# SCH_18f4550_2023-06-13.net
KiCad netlist of a schematic drawn in EasyEDA
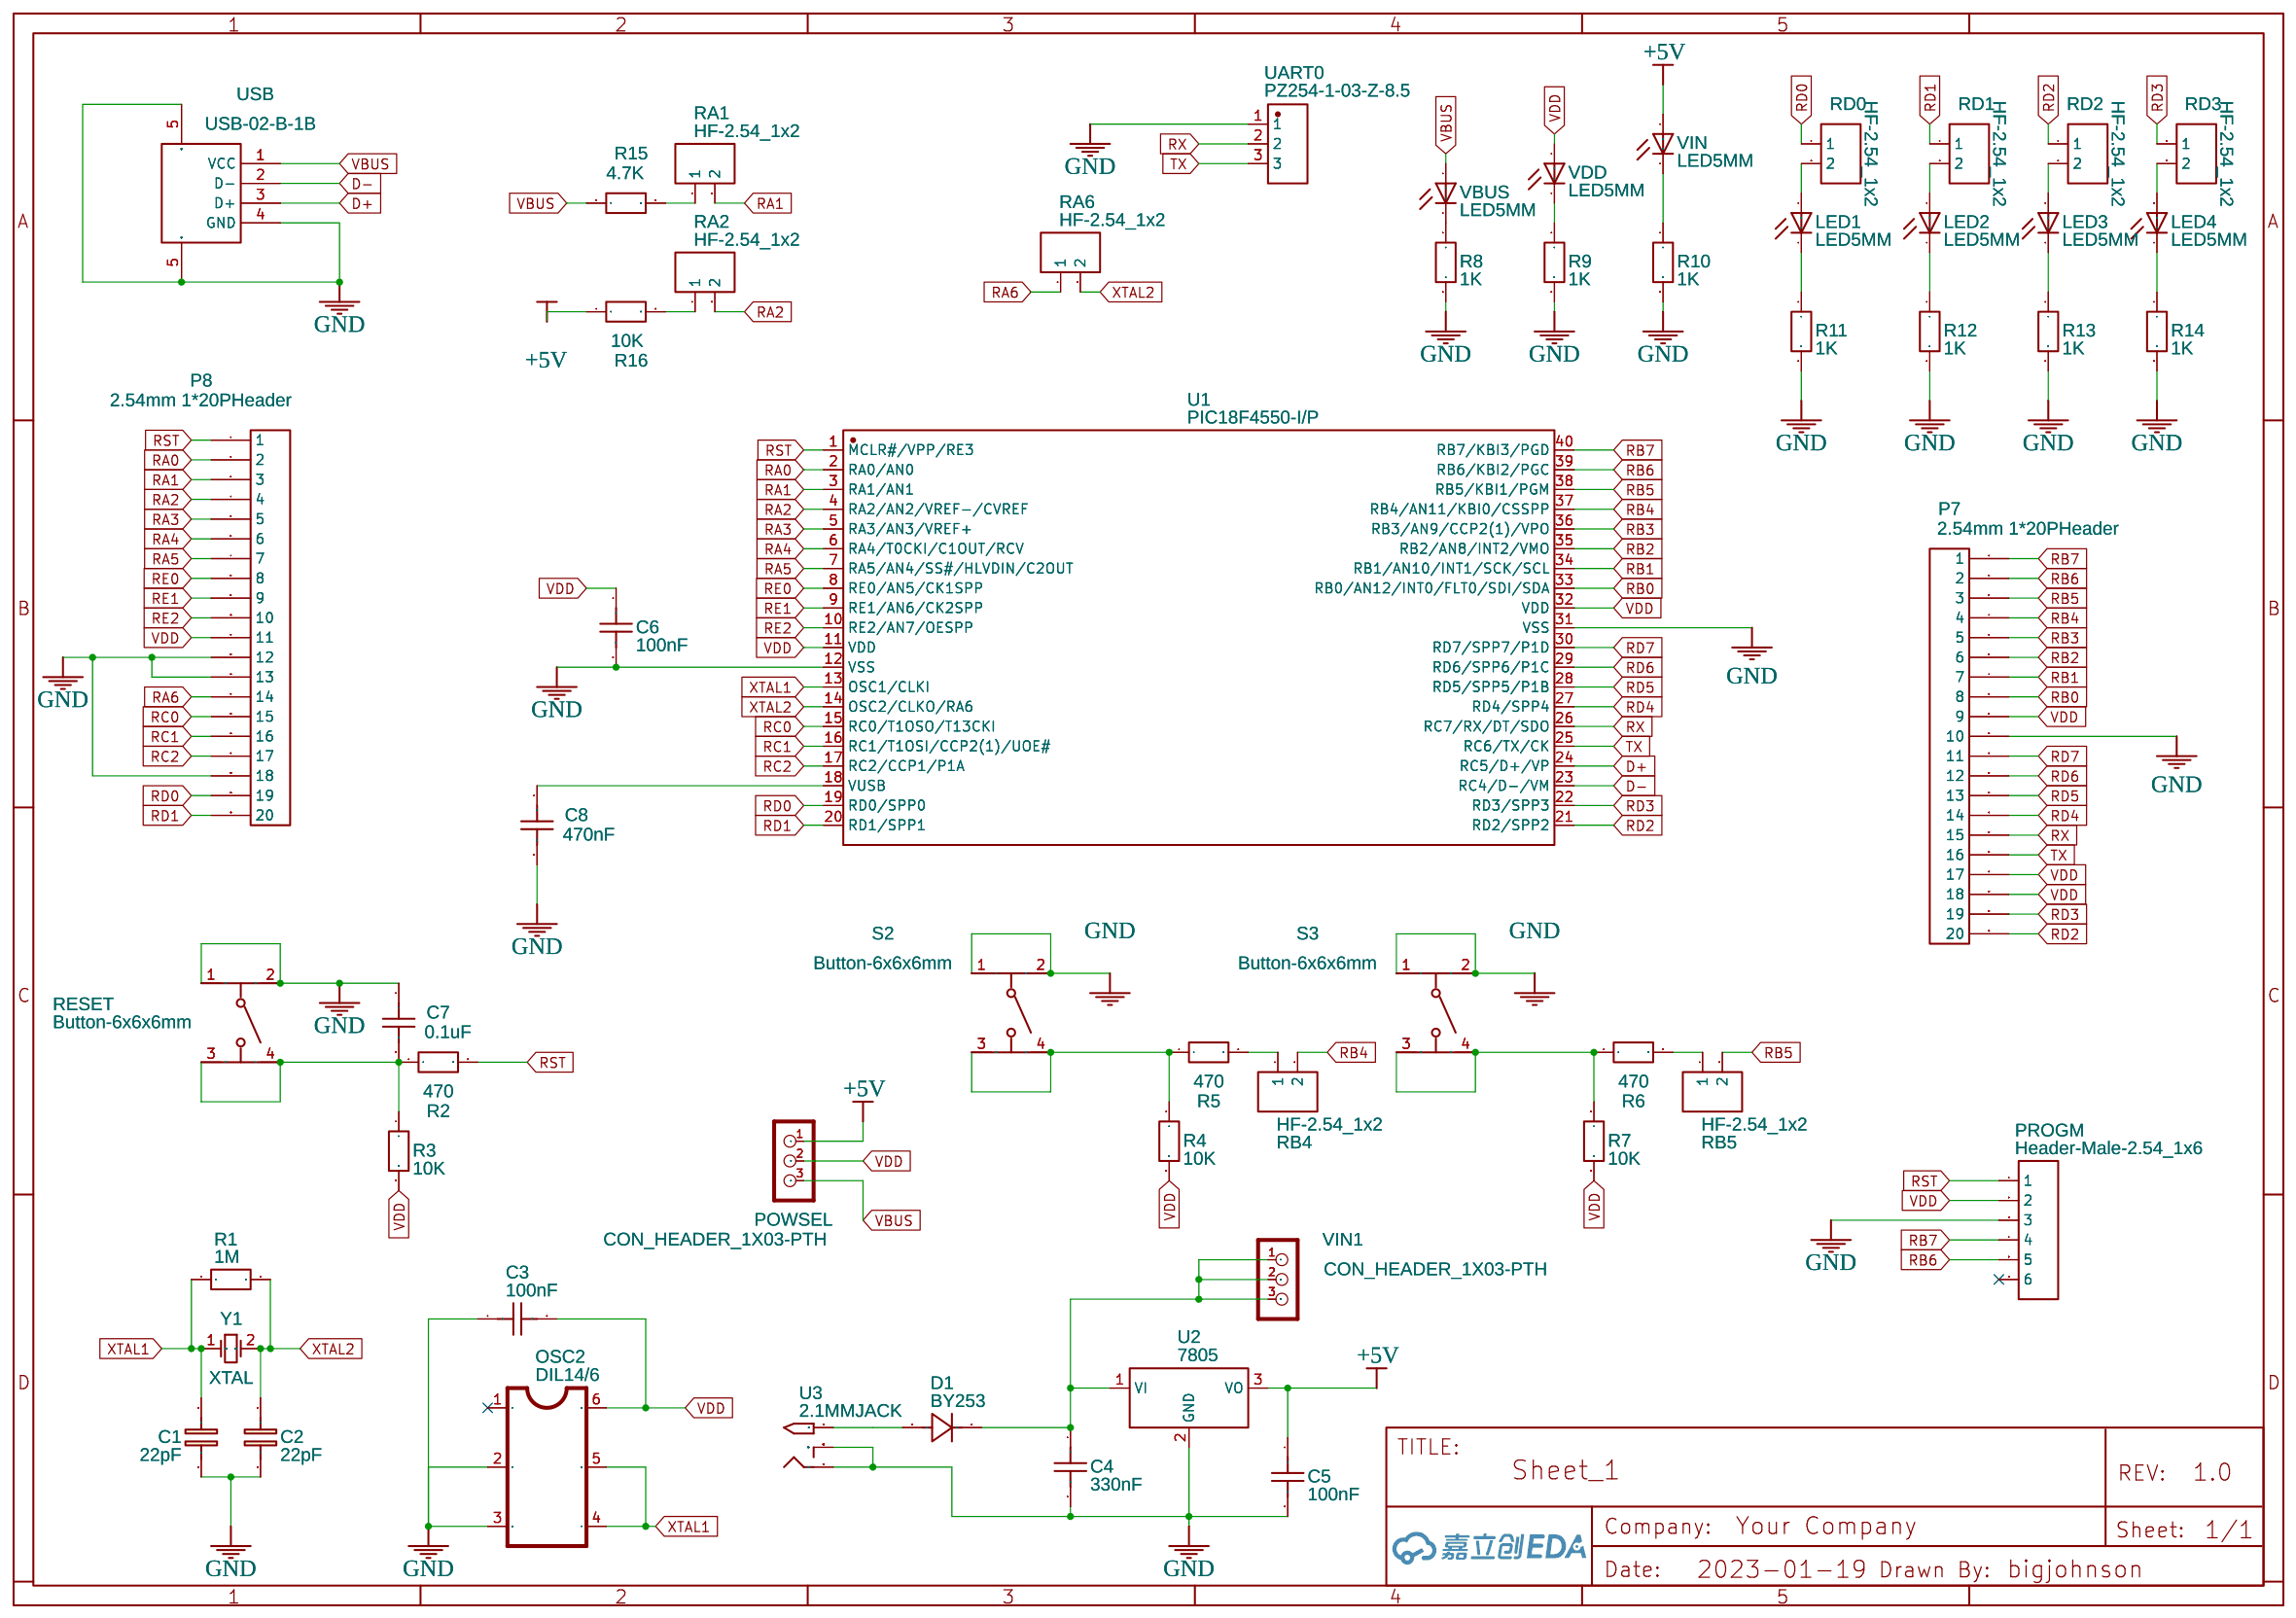
[diagram p0: schematic sheet]

(export (version "E")
  (design (tool "Eeschema 10.0.6"))
  (components
    (comp (ref "C1")
      (value "22pF")
      (fields (field (name "BOM_Supplier Part") "9000274010"))
      (libsource (lib "") (part "20pF copy"))
    )
    (comp (ref "C2")
      (value "22pF")
      (fields (field (name "BOM_Supplier Part") "9000274010"))
      (libsource (lib "") (part "20pF copy"))
    )
    (comp (ref "C3")
      (value "100nF")
      (fields
        (field (name "BOM_Manufacturer Part") "CT4-0805B103 K500")
        (field (name "BOM_Supplier Part") "C8033")
      )
      (libsource (lib "") (part "CT4-0805B103 K500_1"))
    )
    (comp (ref "C4")
      (value "330nF")
      (fields
        (field (name "BOM_Manufacturer Part") "CT4-0805B103 K500")
        (field (name "BOM_Supplier Part") "C8033")
      )
      (libsource (lib "") (part "CT4-0805B103 K500"))
    )
    (comp (ref "C5")
      (value "100nF")
      (fields
        (field (name "BOM_Manufacturer Part") "CT4-0805B103 K500")
        (field (name "BOM_Supplier Part") "C8033")
      )
      (libsource (lib "") (part "CT4-0805B103 K500"))
    )
    (comp (ref "C6")
      (value "100nF")
      (fields
        (field (name "BOM_Manufacturer Part") "CT4-0805B103 K500")
        (field (name "BOM_Supplier Part") "C8033")
      )
      (libsource (lib "") (part "CT4-0805B103 K500"))
    )
    (comp (ref "C7")
      (value "0.1uF")
      (fields
        (field (name "BOM_Manufacturer Part") "CT4-0805B103 K500")
        (field (name "BOM_Supplier Part") "C8033")
      )
      (libsource (lib "") (part "CT4-0805B103 K500"))
    )
    (comp (ref "C8")
      (value "470nF")
      (fields
        (field (name "BOM_Manufacturer Part") "CT4-0805B103 K500")
        (field (name "BOM_Supplier Part") "C8033")
      )
      (libsource (lib "") (part "CT4-0805B103 K500"))
    )
    (comp (ref "D1")
      (value "BY253")
      (fields (field (name "BOM_Manufacturer Part") "MUR460") (field (name "BOM_Supplier Part") "C2990844"))
      (libsource (lib "") (part "MUR460_C2990844"))
    )
    (comp (ref "LED1") (value "LED5MM") (libsource (lib "") (part "LED5MM")))
    (comp (ref "LED2") (value "LED5MM") (libsource (lib "") (part "LED5MM")))
    (comp (ref "LED3") (value "LED5MM") (libsource (lib "") (part "LED5MM")))
    (comp (ref "LED4") (value "LED5MM") (libsource (lib "") (part "LED5MM")))
    (comp (ref "OSC2") (value "DIL14/6") (libsource (lib "") (part "DIL14/3")))
    (comp (ref "P7")
      (value "2.54mm 1*20PHeader")
      (fields (field (name "BOM_Supplier Part") "C50981"))
      (libsource (lib "") (part "2.54mm 1*20PHeader"))
    )
    (comp (ref "P8")
      (value "2.54mm 1*20PHeader")
      (fields (field (name "BOM_Supplier Part") "C50981"))
      (libsource (lib "") (part "2.54mm 1*20PHeader_1"))
    )
    (comp (ref "POWSEL") (value "CON_HEADER_1X03-PTH") (libsource (lib "") (part "CON_HEADER_1X03-PTH")))
    (comp (ref "PROGM")
      (value "Header-Male-2.54_1x6")
      (fields
        (field (name "BOM_Manufacturer Part") "2.54-1x6P直针")
        (field (name "BOM_Supplier Part") "C37208")
      )
      (libsource (lib "") (part "Header-Male-2.54_1x6"))
    )
    (comp (ref "R1") (value "1M") (libsource (lib "") (part "Res_AXIAL-0.4(1/4W)_EU_1")))
    (comp (ref "R2") (value "470") (libsource (lib "") (part "Res_AXIAL-0.4(1/4W)_EU_1")))
    (comp (ref "R3") (value "10K") (libsource (lib "") (part "Res_AXIAL-0.4(1/4W)_EU")))
    (comp (ref "R4") (value "10K") (libsource (lib "") (part "Res_AXIAL-0.4(1/4W)_EU")))
    (comp (ref "R5") (value "470") (libsource (lib "") (part "Res_AXIAL-0.4(1/4W)_EU_1")))
    (comp (ref "R6") (value "470") (libsource (lib "") (part "Res_AXIAL-0.4(1/4W)_EU_1")))
    (comp (ref "R7") (value "10K") (libsource (lib "") (part "Res_AXIAL-0.4(1/4W)_EU")))
    (comp (ref "R8") (value "1K") (libsource (lib "") (part "Res_AXIAL-0.4(1/4W)_EU")))
    (comp (ref "R9") (value "1K") (libsource (lib "") (part "Res_AXIAL-0.4(1/4W)_EU")))
    (comp (ref "R10") (value "1K") (libsource (lib "") (part "Res_AXIAL-0.4(1/4W)_EU")))
    (comp (ref "R11") (value "1K") (libsource (lib "") (part "Res_AXIAL-0.4(1/4W)_EU")))
    (comp (ref "R12") (value "1K") (libsource (lib "") (part "Res_AXIAL-0.4(1/4W)_EU")))
    (comp (ref "R13") (value "1K") (libsource (lib "") (part "Res_AXIAL-0.4(1/4W)_EU")))
    (comp (ref "R14") (value "1K") (libsource (lib "") (part "Res_AXIAL-0.4(1/4W)_EU")))
    (comp (ref "R15") (value "4.7K") (libsource (lib "") (part "Res_AXIAL-0.4(1/4W)_EU_1")))
    (comp (ref "R16") (value "10K") (libsource (lib "") (part "Res_AXIAL-0.4(1/4W)_EU_1")))
    (comp (ref "RA1")
      (value "HF-2.54_1x2")
      (fields (field (name "BOM_Manufacturer Part") "2.54-1*2P母") (field (name "BOM_Supplier Part") "C49661"))
      (libsource (lib "") (part "Header-Female-2.54_1x2"))
    )
    (comp (ref "RA2")
      (value "HF-2.54_1x2")
      (fields (field (name "BOM_Manufacturer Part") "2.54-1*2P母") (field (name "BOM_Supplier Part") "C49661"))
      (libsource (lib "") (part "Header-Female-2.54_1x2"))
    )
    (comp (ref "RA6")
      (value "HF-2.54_1x2")
      (fields (field (name "BOM_Manufacturer Part") "2.54-1*2P母") (field (name "BOM_Supplier Part") "C49661"))
      (libsource (lib "") (part "Header-Female-2.54_1x2"))
    )
    (comp (ref "RB4")
      (value "HF-2.54_1x2")
      (fields (field (name "BOM_Manufacturer Part") "2.54-1*2P母") (field (name "BOM_Supplier Part") "C49661"))
      (libsource (lib "") (part "Header-Female-2.54_1x2_2"))
    )
    (comp (ref "RB5")
      (value "HF-2.54_1x2")
      (fields (field (name "BOM_Manufacturer Part") "2.54-1*2P母") (field (name "BOM_Supplier Part") "C49661"))
      (libsource (lib "") (part "Header-Female-2.54_1x2_2"))
    )
    (comp (ref "RD0")
      (value "HF-2.54_1x2")
      (fields (field (name "BOM_Manufacturer Part") "2.54-1*2P母") (field (name "BOM_Supplier Part") "C49661"))
      (libsource (lib "") (part "Header-Female-2.54_1x2_1"))
    )
    (comp (ref "RD1")
      (value "HF-2.54_1x2")
      (fields (field (name "BOM_Manufacturer Part") "2.54-1*2P母") (field (name "BOM_Supplier Part") "C49661"))
      (libsource (lib "") (part "Header-Female-2.54_1x2_1"))
    )
    (comp (ref "RD2")
      (value "HF-2.54_1x2")
      (fields (field (name "BOM_Manufacturer Part") "2.54-1*2P母") (field (name "BOM_Supplier Part") "C49661"))
      (libsource (lib "") (part "Header-Female-2.54_1x2_1"))
    )
    (comp (ref "RD3")
      (value "HF-2.54_1x2")
      (fields (field (name "BOM_Manufacturer Part") "2.54-1*2P母") (field (name "BOM_Supplier Part") "C49661"))
      (libsource (lib "") (part "Header-Female-2.54_1x2_1"))
    )
    (comp (ref "RESET")
      (value "Button-6x6x6mm")
      (fields
        (field (name "BOM_Manufacturer Part") "Switch,6*6*6Plastic head,260G, 0.25mm,Straight line")
        (field (name "BOM_Supplier Part") "C71836")
      )
      (libsource (lib "") (part "Button-6x6x6mm_1"))
    )
    (comp (ref "S2")
      (value "Button-6x6x6mm")
      (fields
        (field (name "BOM_Manufacturer Part") "Switch,6*6*6Plastic head,260G, 0.25mm,Straight line")
        (field (name "BOM_Supplier Part") "C71836")
      )
      (libsource (lib "") (part "Button-6x6x6mm"))
    )
    (comp (ref "S3")
      (value "Button-6x6x6mm")
      (fields
        (field (name "BOM_Manufacturer Part") "Switch,6*6*6Plastic head,260G, 0.25mm,Straight line")
        (field (name "BOM_Supplier Part") "C71836")
      )
      (libsource (lib "") (part "Button-6x6x6mm"))
    )
    (comp (ref "U1")
      (value "PIC18F4550-I/P")
      (fields (field (name "BOM_Supplier Part") "C648001"))
      (libsource (lib "") (part "PIC18F4550-I/P"))
    )
    (comp (ref "U2")
      (value "7805")
      (fields (field (name "BOM_Supplier Part") "C305416"))
      (libsource (lib "") (part "7805"))
    )
    (comp (ref "U3") (value "2.1MMJACK") (libsource (lib "") (part "2.1MMJACK")))
    (comp (ref "UART0")
      (value "PZ254-1-03-Z-8.5")
      (fields (field (name "BOM_Supplier Part") "C2894926"))
      (libsource (lib "") (part "PZ254-1-03-Z-8.5"))
    )
    (comp (ref "USB")
      (value "USB-02-B-1B")
      (fields (field (name "BOM_Supplier Part") "C718028"))
      (libsource (lib "") (part "USB-02-B-1B"))
    )
    (comp (ref "VBUS") (value "LED5MM") (libsource (lib "") (part "LED5MM_3")))
    (comp (ref "VDD") (value "LED5MM") (libsource (lib "") (part "LED5MM_1")))
    (comp (ref "VIN") (value "LED5MM") (libsource (lib "") (part "LED5MM_2")))
    (comp (ref "VIN1") (value "CON_HEADER_1X03-PTH") (libsource (lib "") (part "CON_HEADER_1X03-PTH_1")))
    (comp (ref "Y1") (value "XTAL") (libsource (lib "") (part "XTAL")))
  )
  (nets
    (net (code "1") (name "+5V") (class "Default")
      (node (ref "C5") (pin "1") (pinfunction "1_1") (pintype "unspecified"))
      (node (ref "POWSEL") (pin "1") (pinfunction "1_1") (pintype "unspecified"))
      (node (ref "R16") (pin "1") (pinfunction "1_1") (pintype "unspecified"))
      (node (ref "U2") (pin "3") (pinfunction "VO_3") (pintype "unspecified"))
      (node (ref "VIN") (pin "A") (pinfunction "A_A") (pintype "unspecified"))
    )
    (net (code "2") (name "D+") (class "Default")
      (node (ref "U1") (pin "24") (pinfunction "RC5/D+/VP_24") (pintype "unspecified"))
      (node (ref "USB") (pin "3") (pinfunction "D+_3") (pintype "input"))
    )
    (net (code "3") (name "D-") (class "Default")
      (node (ref "U1") (pin "23") (pinfunction "RC4/D-/VM_23") (pintype "unspecified"))
      (node (ref "USB") (pin "2") (pinfunction "D-_2") (pintype "input"))
    )
    (net (code "4") (name "GND") (class "Default")
      (node (ref "C1") (pin "2") (pinfunction "1_2") (pintype "unspecified"))
      (node (ref "C2") (pin "2") (pinfunction "1_2") (pintype "unspecified"))
      (node (ref "C3") (pin "1") (pinfunction "1_1") (pintype "unspecified"))
      (node (ref "C4") (pin "2") (pinfunction "2_2") (pintype "unspecified"))
      (node (ref "C5") (pin "2") (pinfunction "2_2") (pintype "unspecified"))
      (node (ref "C6") (pin "2") (pinfunction "2_2") (pintype "unspecified"))
      (node (ref "C7") (pin "1") (pinfunction "1_1") (pintype "unspecified"))
      (node (ref "C8") (pin "2") (pinfunction "2_2") (pintype "unspecified"))
      (node (ref "OSC2") (pin "2") (pinfunction "2_2") (pintype "unspecified"))
      (node (ref "OSC2") (pin "3") (pinfunction "3_3") (pintype "unspecified"))
      (node (ref "P7") (pin "10") (pinfunction "10_10") (pintype "input"))
      (node (ref "P8") (pin "12") (pinfunction "12_12") (pintype "input"))
      (node (ref "P8") (pin "13") (pinfunction "13_13") (pintype "input"))
      (node (ref "P8") (pin "18") (pinfunction "18_18") (pintype "input"))
      (node (ref "PROGM") (pin "3") (pinfunction "3_3") (pintype "input"))
      (node (ref "R10") (pin "2") (pinfunction "2_2") (pintype "unspecified"))
      (node (ref "R11") (pin "2") (pinfunction "2_2") (pintype "unspecified"))
      (node (ref "R12") (pin "2") (pinfunction "2_2") (pintype "unspecified"))
      (node (ref "R13") (pin "2") (pinfunction "2_2") (pintype "unspecified"))
      (node (ref "R14") (pin "2") (pinfunction "2_2") (pintype "unspecified"))
      (node (ref "R8") (pin "2") (pinfunction "2_2") (pintype "unspecified"))
      (node (ref "R9") (pin "2") (pinfunction "2_2") (pintype "unspecified"))
      (node (ref "RESET") (pin "1") (pinfunction "1_1") (pintype "unspecified"))
      (node (ref "RESET") (pin "2") (pinfunction "2_2") (pintype "unspecified"))
      (node (ref "S2") (pin "1") (pinfunction "1_1") (pintype "unspecified"))
      (node (ref "S2") (pin "2") (pinfunction "2_2") (pintype "unspecified"))
      (node (ref "S3") (pin "1") (pinfunction "1_1") (pintype "unspecified"))
      (node (ref "S3") (pin "2") (pinfunction "2_2") (pintype "unspecified"))
      (node (ref "U1") (pin "12") (pinfunction "VSS_12") (pintype "unspecified"))
      (node (ref "U1") (pin "31") (pinfunction "VSS_31") (pintype "unspecified"))
      (node (ref "U2") (pin "2") (pinfunction "GND_2") (pintype "unspecified"))
      (node (ref "U3") (pin "RING") (pinfunction "RING_RING") (pintype "unspecified"))
      (node (ref "U3") (pin "RING_SW") (pinfunction "RING_SW_RING_SW") (pintype "unspecified"))
      (node (ref "UART0") (pin "1") (pinfunction "1_1") (pintype "unspecified"))
      (node (ref "USB") (pin "4") (pinfunction "GND_4") (pintype "input"))
      (node (ref "USB") (pin "5") (pinfunction "SHLD_5") (pintype "unspecified"))
    )
    (net (code "5") (name "Net-(C7-Pad2)") (class "Default")
      (node (ref "C7") (pin "2") (pinfunction "2_2") (pintype "unspecified"))
      (node (ref "R2") (pin "1") (pinfunction "1_1") (pintype "unspecified"))
      (node (ref "R3") (pin "1") (pinfunction "1_1") (pintype "unspecified"))
      (node (ref "RESET") (pin "3") (pinfunction "3_3") (pintype "unspecified"))
      (node (ref "RESET") (pin "4") (pinfunction "4_4") (pintype "unspecified"))
    )
    (net (code "6") (name "Net-(D1-A)") (class "Default")
      (node (ref "D1") (pin "2") (pinfunction "A_2") (pintype "unspecified"))
      (node (ref "U3") (pin "TIP") (pinfunction "TIP_TIP") (pintype "unspecified"))
    )
    (net (code "7") (name "Net-(D1-K)") (class "Default")
      (node (ref "C4") (pin "1") (pinfunction "1_1") (pintype "unspecified"))
      (node (ref "D1") (pin "1") (pinfunction "K_1") (pintype "unspecified"))
      (node (ref "U2") (pin "1") (pinfunction "VI_1") (pintype "unspecified"))
      (node (ref "VIN1") (pin "1") (pinfunction "1_1") (pintype "unspecified"))
      (node (ref "VIN1") (pin "2") (pinfunction "2_2") (pintype "unspecified"))
      (node (ref "VIN1") (pin "3") (pinfunction "3_3") (pintype "unspecified"))
    )
    (net (code "8") (name "Net-(LED1-C)") (class "Default")
      (node (ref "LED1") (pin "K") (pinfunction "C_K") (pintype "unspecified"))
      (node (ref "R11") (pin "1") (pinfunction "1_1") (pintype "unspecified"))
    )
    (net (code "9") (name "Net-(LED1-PadA)") (class "Default")
      (node (ref "LED1") (pin "A") (pinfunction "A_A") (pintype "unspecified"))
      (node (ref "RD0") (pin "2") (pinfunction "2_2") (pintype "input"))
    )
    (net (code "10") (name "Net-(LED2-C)") (class "Default")
      (node (ref "LED2") (pin "K") (pinfunction "C_K") (pintype "unspecified"))
      (node (ref "R12") (pin "1") (pinfunction "1_1") (pintype "unspecified"))
    )
    (net (code "11") (name "Net-(LED2-PadA)") (class "Default")
      (node (ref "LED2") (pin "A") (pinfunction "A_A") (pintype "unspecified"))
      (node (ref "RD1") (pin "2") (pinfunction "2_2") (pintype "input"))
    )
    (net (code "12") (name "Net-(LED3-C)") (class "Default")
      (node (ref "LED3") (pin "K") (pinfunction "C_K") (pintype "unspecified"))
      (node (ref "R13") (pin "1") (pinfunction "1_1") (pintype "unspecified"))
    )
    (net (code "13") (name "Net-(LED3-PadA)") (class "Default")
      (node (ref "LED3") (pin "A") (pinfunction "A_A") (pintype "unspecified"))
      (node (ref "RD2") (pin "2") (pinfunction "2_2") (pintype "input"))
    )
    (net (code "14") (name "Net-(LED4-C)") (class "Default")
      (node (ref "LED4") (pin "K") (pinfunction "C_K") (pintype "unspecified"))
      (node (ref "R14") (pin "1") (pinfunction "1_1") (pintype "unspecified"))
    )
    (net (code "15") (name "Net-(LED4-PadA)") (class "Default")
      (node (ref "LED4") (pin "A") (pinfunction "A_A") (pintype "unspecified"))
      (node (ref "RD3") (pin "2") (pinfunction "2_2") (pintype "input"))
    )
    (net (code "16") (name "Net-(R4-Pad1)") (class "Default")
      (node (ref "R4") (pin "1") (pinfunction "1_1") (pintype "unspecified"))
      (node (ref "R5") (pin "1") (pinfunction "1_1") (pintype "unspecified"))
      (node (ref "S2") (pin "3") (pinfunction "3_3") (pintype "unspecified"))
      (node (ref "S2") (pin "4") (pinfunction "4_4") (pintype "unspecified"))
    )
    (net (code "17") (name "Net-(R5-Pad2)") (class "Default")
      (node (ref "R5") (pin "2") (pinfunction "2_2") (pintype "unspecified"))
      (node (ref "RB4") (pin "1") (pinfunction "1_1") (pintype "input"))
    )
    (net (code "18") (name "Net-(R6-Pad1)") (class "Default")
      (node (ref "R6") (pin "1") (pinfunction "1_1") (pintype "unspecified"))
      (node (ref "R7") (pin "1") (pinfunction "1_1") (pintype "unspecified"))
      (node (ref "S3") (pin "3") (pinfunction "3_3") (pintype "unspecified"))
      (node (ref "S3") (pin "4") (pinfunction "4_4") (pintype "unspecified"))
    )
    (net (code "19") (name "Net-(R6-Pad2)") (class "Default")
      (node (ref "R6") (pin "2") (pinfunction "2_2") (pintype "unspecified"))
      (node (ref "RB5") (pin "1") (pinfunction "1_1") (pintype "input"))
    )
    (net (code "20") (name "Net-(R15-Pad2)") (class "Default")
      (node (ref "R15") (pin "2") (pinfunction "2_2") (pintype "unspecified"))
      (node (ref "RA1") (pin "1") (pinfunction "1_1") (pintype "input"))
    )
    (net (code "21") (name "Net-(R16-Pad2)") (class "Default")
      (node (ref "R16") (pin "2") (pinfunction "2_2") (pintype "unspecified"))
      (node (ref "RA2") (pin "1") (pinfunction "1_1") (pintype "input"))
    )
    (net (code "22") (name "Net-(U1-VUSB)") (class "Default")
      (node (ref "C8") (pin "1") (pinfunction "1_1") (pintype "unspecified"))
      (node (ref "U1") (pin "18") (pinfunction "VUSB_18") (pintype "unspecified"))
    )
    (net (code "23") (name "Net-(VBUS-C)") (class "Default")
      (node (ref "R8") (pin "1") (pinfunction "1_1") (pintype "unspecified"))
      (node (ref "VBUS") (pin "K") (pinfunction "C_K") (pintype "unspecified"))
    )
    (net (code "24") (name "Net-(VDD-C)") (class "Default")
      (node (ref "R9") (pin "1") (pinfunction "1_1") (pintype "unspecified"))
      (node (ref "VDD") (pin "K") (pinfunction "C_K") (pintype "unspecified"))
    )
    (net (code "25") (name "Net-(VIN-C)") (class "Default")
      (node (ref "R10") (pin "1") (pinfunction "1_1") (pintype "unspecified"))
      (node (ref "VIN") (pin "K") (pinfunction "C_K") (pintype "unspecified"))
    )
    (net (code "26") (name "RA0") (class "Default")
      (node (ref "P8") (pin "2") (pinfunction "2_2") (pintype "input"))
      (node (ref "U1") (pin "2") (pinfunction "RA0/AN0_2") (pintype "unspecified"))
    )
    (net (code "27") (name "RA1") (class "Default")
      (node (ref "P8") (pin "3") (pinfunction "3_3") (pintype "input"))
      (node (ref "RA1") (pin "2") (pinfunction "2_2") (pintype "input"))
      (node (ref "U1") (pin "3") (pinfunction "RA1/AN1_3") (pintype "unspecified"))
    )
    (net (code "28") (name "RA2") (class "Default")
      (node (ref "P8") (pin "4") (pinfunction "4_4") (pintype "input"))
      (node (ref "RA2") (pin "2") (pinfunction "2_2") (pintype "input"))
      (node (ref "U1") (pin "4") (pinfunction "RA2/AN2/VREF-/CVREF_4") (pintype "unspecified"))
    )
    (net (code "29") (name "RA3") (class "Default")
      (node (ref "P8") (pin "5") (pinfunction "5_5") (pintype "input"))
      (node (ref "U1") (pin "5") (pinfunction "RA3/AN3/VREF+_5") (pintype "unspecified"))
    )
    (net (code "30") (name "RA4") (class "Default")
      (node (ref "P8") (pin "6") (pinfunction "6_6") (pintype "input"))
      (node (ref "U1") (pin "6") (pinfunction "RA4/T0CKI/C1OUT/RCV_6") (pintype "unspecified"))
    )
    (net (code "31") (name "RA5") (class "Default")
      (node (ref "P8") (pin "7") (pinfunction "7_7") (pintype "input"))
      (node (ref "U1") (pin "7") (pinfunction "RA5/AN4/SS#/HLVDIN/C2OUT_7") (pintype "unspecified"))
    )
    (net (code "32") (name "RA6") (class "Default")
      (node (ref "P8") (pin "14") (pinfunction "14_14") (pintype "input"))
      (node (ref "RA6") (pin "1") (pinfunction "1_1") (pintype "input"))
    )
    (net (code "33") (name "RB0") (class "Default")
      (node (ref "P7") (pin "8") (pinfunction "8_8") (pintype "input"))
      (node (ref "U1") (pin "33") (pinfunction "RB0/AN12/INT0/FLT0/SDI/SDA_33") (pintype "unspecified"))
    )
    (net (code "34") (name "RB1") (class "Default")
      (node (ref "P7") (pin "7") (pinfunction "7_7") (pintype "input"))
      (node (ref "U1") (pin "34") (pinfunction "RB1/AN10/INT1/SCK/SCL_34") (pintype "unspecified"))
    )
    (net (code "35") (name "RB2") (class "Default")
      (node (ref "P7") (pin "6") (pinfunction "6_6") (pintype "input"))
      (node (ref "U1") (pin "35") (pinfunction "RB2/AN8/INT2/VMO_35") (pintype "unspecified"))
    )
    (net (code "36") (name "RB3") (class "Default")
      (node (ref "P7") (pin "5") (pinfunction "5_5") (pintype "input"))
      (node (ref "U1") (pin "36") (pinfunction "RB3/AN9/CCP2(1)/VPO_36") (pintype "unspecified"))
    )
    (net (code "37") (name "RB4") (class "Default")
      (node (ref "P7") (pin "4") (pinfunction "4_4") (pintype "input"))
      (node (ref "RB4") (pin "2") (pinfunction "2_2") (pintype "input"))
      (node (ref "U1") (pin "37") (pinfunction "RB4/AN11/KBI0/CSSPP_37") (pintype "unspecified"))
    )
    (net (code "38") (name "RB5") (class "Default")
      (node (ref "P7") (pin "3") (pinfunction "3_3") (pintype "input"))
      (node (ref "RB5") (pin "2") (pinfunction "2_2") (pintype "input"))
      (node (ref "U1") (pin "38") (pinfunction "RB5/KBI1/PGM_38") (pintype "unspecified"))
    )
    (net (code "39") (name "RB6") (class "Default")
      (node (ref "P7") (pin "2") (pinfunction "2_2") (pintype "input"))
      (node (ref "PROGM") (pin "5") (pinfunction "5_5") (pintype "input"))
      (node (ref "U1") (pin "39") (pinfunction "RB6/KBI2/PGC_39") (pintype "unspecified"))
    )
    (net (code "40") (name "RB7") (class "Default")
      (node (ref "P7") (pin "1") (pinfunction "1_1") (pintype "input"))
      (node (ref "PROGM") (pin "4") (pinfunction "4_4") (pintype "input"))
      (node (ref "U1") (pin "40") (pinfunction "RB7/KBI3/PGD_40") (pintype "unspecified"))
    )
    (net (code "41") (name "RC0") (class "Default")
      (node (ref "P8") (pin "15") (pinfunction "15_15") (pintype "input"))
      (node (ref "U1") (pin "15") (pinfunction "RC0/T1OSO/T13CKI_15") (pintype "unspecified"))
    )
    (net (code "42") (name "RC1") (class "Default")
      (node (ref "P8") (pin "16") (pinfunction "16_16") (pintype "input"))
      (node (ref "U1") (pin "16") (pinfunction "RC1/T1OSI/CCP2(1)/UOE#_16") (pintype "unspecified"))
    )
    (net (code "43") (name "RC2") (class "Default")
      (node (ref "P8") (pin "17") (pinfunction "17_17") (pintype "input"))
      (node (ref "U1") (pin "17") (pinfunction "RC2/CCP1/P1A_17") (pintype "unspecified"))
    )
    (net (code "44") (name "RD0") (class "Default")
      (node (ref "P8") (pin "19") (pinfunction "19_19") (pintype "input"))
      (node (ref "RD0") (pin "1") (pinfunction "1_1") (pintype "input"))
      (node (ref "U1") (pin "19") (pinfunction "RD0/SPP0_19") (pintype "unspecified"))
    )
    (net (code "45") (name "RD1") (class "Default")
      (node (ref "P8") (pin "20") (pinfunction "20_20") (pintype "input"))
      (node (ref "RD1") (pin "1") (pinfunction "1_1") (pintype "input"))
      (node (ref "U1") (pin "20") (pinfunction "RD1/SPP1_20") (pintype "unspecified"))
    )
    (net (code "46") (name "RD2") (class "Default")
      (node (ref "P7") (pin "20") (pinfunction "20_20") (pintype "input"))
      (node (ref "RD2") (pin "1") (pinfunction "1_1") (pintype "input"))
      (node (ref "U1") (pin "21") (pinfunction "RD2/SPP2_21") (pintype "unspecified"))
    )
    (net (code "47") (name "RD3") (class "Default")
      (node (ref "P7") (pin "19") (pinfunction "19_19") (pintype "input"))
      (node (ref "RD3") (pin "1") (pinfunction "1_1") (pintype "input"))
      (node (ref "U1") (pin "22") (pinfunction "RD3/SPP3_22") (pintype "unspecified"))
    )
    (net (code "48") (name "RD4") (class "Default")
      (node (ref "P7") (pin "14") (pinfunction "14_14") (pintype "input"))
      (node (ref "U1") (pin "27") (pinfunction "RD4/SPP4_27") (pintype "unspecified"))
    )
    (net (code "49") (name "RD5") (class "Default")
      (node (ref "P7") (pin "13") (pinfunction "13_13") (pintype "input"))
      (node (ref "U1") (pin "28") (pinfunction "RD5/SPP5/P1B_28") (pintype "unspecified"))
    )
    (net (code "50") (name "RD6") (class "Default")
      (node (ref "P7") (pin "12") (pinfunction "12_12") (pintype "input"))
      (node (ref "U1") (pin "29") (pinfunction "RD6/SPP6/P1C_29") (pintype "unspecified"))
    )
    (net (code "51") (name "RD7") (class "Default")
      (node (ref "P7") (pin "11") (pinfunction "11_11") (pintype "input"))
      (node (ref "U1") (pin "30") (pinfunction "RD7/SPP7/P1D_30") (pintype "unspecified"))
    )
    (net (code "52") (name "RE0") (class "Default")
      (node (ref "P8") (pin "8") (pinfunction "8_8") (pintype "input"))
      (node (ref "U1") (pin "8") (pinfunction "RE0/AN5/CK1SPP_8") (pintype "unspecified"))
    )
    (net (code "53") (name "RE1") (class "Default")
      (node (ref "P8") (pin "9") (pinfunction "9_9") (pintype "input"))
      (node (ref "U1") (pin "9") (pinfunction "RE1/AN6/CK2SPP_9") (pintype "unspecified"))
    )
    (net (code "54") (name "RE2") (class "Default")
      (node (ref "P8") (pin "10") (pinfunction "10_10") (pintype "input"))
      (node (ref "U1") (pin "10") (pinfunction "RE2/AN7/OESPP_10") (pintype "unspecified"))
    )
    (net (code "55") (name "RST") (class "Default")
      (node (ref "P8") (pin "1") (pinfunction "1_1") (pintype "input"))
      (node (ref "PROGM") (pin "1") (pinfunction "1_1") (pintype "input"))
      (node (ref "R2") (pin "2") (pinfunction "2_2") (pintype "unspecified"))
      (node (ref "U1") (pin "1") (pinfunction "MCLR#/VPP/RE3_1") (pintype "unspecified"))
    )
    (net (code "56") (name "RX") (class "Default")
      (node (ref "P7") (pin "15") (pinfunction "15_15") (pintype "input"))
      (node (ref "U1") (pin "26") (pinfunction "RC7/RX/DT/SDO_26") (pintype "unspecified"))
      (node (ref "UART0") (pin "2") (pinfunction "2_2") (pintype "unspecified"))
    )
    (net (code "57") (name "TX") (class "Default")
      (node (ref "P7") (pin "16") (pinfunction "16_16") (pintype "input"))
      (node (ref "U1") (pin "25") (pinfunction "RC6/TX/CK_25") (pintype "unspecified"))
      (node (ref "UART0") (pin "3") (pinfunction "3_3") (pintype "unspecified"))
    )
    (net (code "58") (name "VBUS") (class "Default")
      (node (ref "POWSEL") (pin "3") (pinfunction "3_3") (pintype "unspecified"))
      (node (ref "R15") (pin "1") (pinfunction "1_1") (pintype "unspecified"))
      (node (ref "USB") (pin "1") (pinfunction "VCC_1") (pintype "input"))
      (node (ref "VBUS") (pin "A") (pinfunction "A_A") (pintype "unspecified"))
    )
    (net (code "59") (name "VDD") (class "Default")
      (node (ref "C3") (pin "2") (pinfunction "2_2") (pintype "unspecified"))
      (node (ref "C6") (pin "1") (pinfunction "1_1") (pintype "unspecified"))
      (node (ref "OSC2") (pin "6") (pinfunction "6_6") (pintype "unspecified"))
      (node (ref "P7") (pin "17") (pinfunction "17_17") (pintype "input"))
      (node (ref "P7") (pin "18") (pinfunction "18_18") (pintype "input"))
      (node (ref "P7") (pin "9") (pinfunction "9_9") (pintype "input"))
      (node (ref "P8") (pin "11") (pinfunction "11_11") (pintype "input"))
      (node (ref "POWSEL") (pin "2") (pinfunction "2_2") (pintype "unspecified"))
      (node (ref "PROGM") (pin "2") (pinfunction "2_2") (pintype "input"))
      (node (ref "R3") (pin "2") (pinfunction "2_2") (pintype "unspecified"))
      (node (ref "R4") (pin "2") (pinfunction "2_2") (pintype "unspecified"))
      (node (ref "R7") (pin "2") (pinfunction "2_2") (pintype "unspecified"))
      (node (ref "U1") (pin "11") (pinfunction "VDD_11") (pintype "unspecified"))
      (node (ref "U1") (pin "32") (pinfunction "VDD_32") (pintype "unspecified"))
      (node (ref "VDD") (pin "A") (pinfunction "A_A") (pintype "unspecified"))
    )
    (net (code "60") (name "XTAL1") (class "Default")
      (node (ref "C1") (pin "1") (pinfunction "1_1") (pintype "unspecified"))
      (node (ref "OSC2") (pin "4") (pinfunction "4_4") (pintype "unspecified"))
      (node (ref "OSC2") (pin "5") (pinfunction "5_5") (pintype "unspecified"))
      (node (ref "R1") (pin "1") (pinfunction "1_1") (pintype "unspecified"))
      (node (ref "U1") (pin "13") (pinfunction "OSC1/CLKI_13") (pintype "unspecified"))
      (node (ref "Y1") (pin "1") (pinfunction "OSC1_1") (pintype "unspecified"))
    )
    (net (code "61") (name "XTAL2") (class "Default")
      (node (ref "C2") (pin "1") (pinfunction "1_1") (pintype "unspecified"))
      (node (ref "R1") (pin "2") (pinfunction "2_2") (pintype "unspecified"))
      (node (ref "RA6") (pin "2") (pinfunction "2_2") (pintype "input"))
      (node (ref "U1") (pin "14") (pinfunction "OSC2/CLKO/RA6_14") (pintype "unspecified"))
      (node (ref "Y1") (pin "2") (pinfunction "OSC2_2") (pintype "unspecified"))
    )
    (net (code "62") (name "unconnected-(OSC2-Pad1)") (class "Default")
      (node (ref "OSC2") (pin "1") (pinfunction "1_1") (pintype "unspecified+no_connect"))
    )
    (net (code "63") (name "unconnected-(PROGM-Pad6)") (class "Default")
      (node (ref "PROGM") (pin "6") (pinfunction "6_6") (pintype "input+no_connect"))
    )
  )
)
